# Clock_Gen.net
KiCad netlist of a schematic drawn in Altium Designer
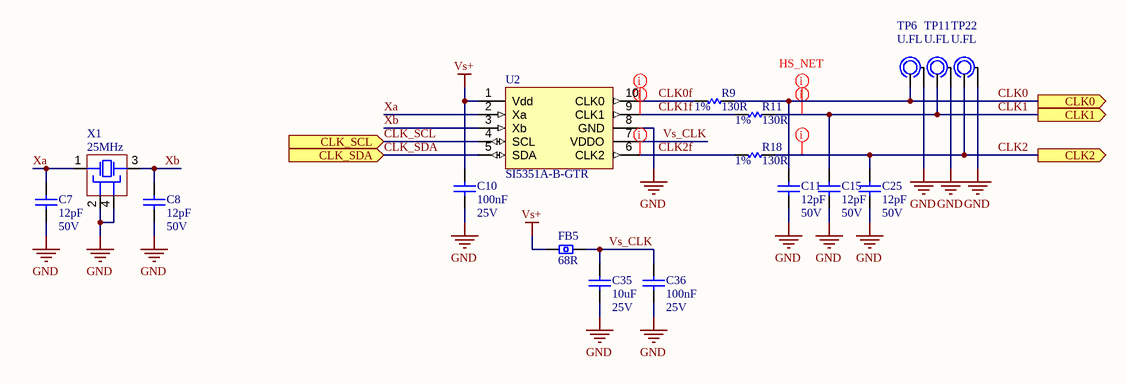
[diagram p0: Clock_Gen.SchDoc]

(export (version "E")
  (design (tool "Eeschema 10.0.6"))
  (components
    (comp (ref "C7")
      (value "12pF")
      (footprint "C0402")
      (description "Ceramic capacitor SMD-0402 12pF /50V C0G# J +-5%, Samsung, RoHS")
      (fields
        (field (name "MANUFACTURER") "Samsung")
        (field (name "MANUFACTURER PART NUMBER") "CL05C120JB5NNNC")
        (field (name "VOLTAGE") "50V")
      )
      (libsource (lib "LaserDiode_Analog") (part "CAP CER 12pF 50V C0G 0402"))
    )
    (comp (ref "C8")
      (value "12pF")
      (footprint "C0402")
      (description "Ceramic capacitor SMD-0402 12pF /50V C0G# J +-5%, Samsung, RoHS")
      (fields
        (field (name "MANUFACTURER") "Samsung")
        (field (name "MANUFACTURER PART NUMBER") "CL05C120JB5NNNC")
        (field (name "VOLTAGE") "50V")
      )
      (libsource (lib "LaserDiode_Analog") (part "CAP CER 12pF 50V C0G 0402"))
    )
    (comp (ref "C10")
      (value "100nF")
      (footprint "C0402")
      (description "Cap Ceramic 0.1uF 25V X5R 10% Pad SMD 0402 85°C T/R / Multi Layer Ceramic Capacitor (MLCC)")
      (fields
        (field (name "MANUFACTURER") "Samsung")
        (field (name "MANUFACTURER PART NUMBER") "CL05A104KA5NNNC")
        (field (name "VOLTAGE RATING") "25V")
      )
      (libsource (lib "OPAMP_DEV_SOT5_6-23") (part "CAP CER 100nF 25V X5R 0402"))
    )
    (comp (ref "C11")
      (value "12pF")
      (footprint "C0402")
      (description "Ceramic capacitor SMD-0402 12pF /50V C0G# J +-5%, Samsung, RoHS")
      (fields
        (field (name "MANUFACTURER") "Samsung")
        (field (name "MANUFACTURER PART NUMBER") "CL05C120JB5NNNC")
        (field (name "VOLTAGE") "50V")
      )
      (libsource (lib "LaserDiode_Analog") (part "CAP CER 12pF 50V C0G 0402"))
    )
    (comp (ref "C15")
      (value "12pF")
      (footprint "C0402")
      (description "Ceramic capacitor SMD-0402 12pF /50V C0G# J +-5%, Samsung, RoHS")
      (fields
        (field (name "MANUFACTURER") "Samsung")
        (field (name "MANUFACTURER PART NUMBER") "CL05C120JB5NNNC")
        (field (name "VOLTAGE") "50V")
      )
      (libsource (lib "LaserDiode_Analog") (part "CAP CER 12pF 50V C0G 0402"))
    )
    (comp (ref "C25")
      (value "12pF")
      (footprint "C0402")
      (description "Ceramic capacitor SMD-0402 12pF /50V C0G# J +-5%, Samsung, RoHS")
      (fields
        (field (name "MANUFACTURER") "Samsung")
        (field (name "MANUFACTURER PART NUMBER") "CL05C120JB5NNNC")
        (field (name "VOLTAGE") "50V")
      )
      (libsource (lib "LaserDiode_Analog") (part "CAP CER 12pF 50V C0G 0402"))
    )
    (comp (ref "C35")
      (value "10uF")
      (footprint "c0805")
      (description "Cap Ceramic 10uF 25V X5R 10% SMD 0805 85°C Embossed T/R")
      (fields
        (field (name "MANUFACTURER") "Samsung")
        (field (name "MANUFACTURER PART NUMBER") "CL21A106KAYNNNE")
        (field (name "VOLTAGE RATING") "25V")
      )
      (libsource (lib "OPAMP_DEV_SOT5_6-23") (part "CAP CER 10uF 25V X5R 0805"))
    )
    (comp (ref "C36")
      (value "100nF")
      (footprint "C0402")
      (description "Cap Ceramic 0.1uF 25V X5R 10% Pad SMD 0402 85°C T/R / Multi Layer Ceramic Capacitor (MLCC)")
      (fields
        (field (name "MANUFACTURER") "Samsung")
        (field (name "MANUFACTURER PART NUMBER") "CL05A104KA5NNNC")
        (field (name "VOLTAGE RATING") "25V")
      )
      (libsource (lib "OPAMP_DEV_SOT5_6-23") (part "CAP CER 100nF 25V X5R 0402"))
    )
    (comp (ref "FB5")
      (value "68R")
      (footprint "FB0402")
      (description "Ferrite Beads Multi-Layer 68Ohm 25% 100MHz 400mA 310mOhm DCR 0402 T/R")
      (fields
        (field (name "MANUFACTURER") "Taiyo Yuden")
        (field (name "MANUFACTURER PART NUMBER") "BK1005LL680-T")
      )
      (libsource (lib "MCU") (part "FB 68R 400mA 310mR 0402"))
    )
    (comp (ref "R9")
      (value "130R")
      (footprint "R0402")
      (description "Res General Purpose Thick Film 0402 130 Ohm 1% 1/16W ±100ppm/°C Molded SMD Paper T/R")
      (fields (field (name "TOLERANCE") "1%"))
      (libsource (lib "LaserDiode_Analog") (part "RES 130R 1% 63mW 0402"))
    )
    (comp (ref "R11")
      (value "130R")
      (footprint "R0402")
      (description "Res General Purpose Thick Film 0402 130 Ohm 1% 1/16W ±100ppm/°C Molded SMD Paper T/R")
      (fields (field (name "TOLERANCE") "1%"))
      (libsource (lib "LaserDiode_Analog") (part "RES 130R 1% 63mW 0402"))
    )
    (comp (ref "R18")
      (value "130R")
      (footprint "R0402")
      (description "Res General Purpose Thick Film 0402 130 Ohm 1% 1/16W ±100ppm/°C Molded SMD Paper T/R")
      (fields (field (name "TOLERANCE") "1%"))
      (libsource (lib "LaserDiode_Analog") (part "RES 130R 1% 63mW 0402"))
    )
    (comp (ref "TP6")
      (value "U.FL")
      (footprint "U.FL")
      (description "CONN U.FL RCPT STR 50 OHM SMD")
      (fields
        (field (name "MANUFACTURER") "Hirose")
        (field (name "MANUFACTURER PART NUMBER") "U.FL-R-SMT-1(80)")
      )
      (libsource (lib "OPAMP_DEV_SOT5_6-23") (part "TP U.FL"))
    )
    (comp (ref "TP11")
      (value "U.FL")
      (footprint "U.FL")
      (description "CONN U.FL RCPT STR 50 OHM SMD")
      (fields
        (field (name "MANUFACTURER") "Hirose")
        (field (name "MANUFACTURER PART NUMBER") "U.FL-R-SMT-1(80)")
      )
      (libsource (lib "OPAMP_DEV_SOT5_6-23") (part "TP U.FL"))
    )
    (comp (ref "TP22")
      (value "U.FL")
      (footprint "U.FL")
      (description "CONN U.FL RCPT STR 50 OHM SMD")
      (fields
        (field (name "MANUFACTURER") "Hirose")
        (field (name "MANUFACTURER PART NUMBER") "U.FL-R-SMT-1(80)")
      )
      (libsource (lib "OPAMP_DEV_SOT5_6-23") (part "TP U.FL"))
    )
    (comp (ref "U2")
      (value "SI5351A-B-GTR")
      (footprint "TSSOP50P490X110-10N")
      (libsource (lib "LaserDiode_Analog") (part "IC CLK GEN 200MHz 3 chan SI5351A-B-GTR"))
    )
    (comp (ref "X1")
      (value "25MHz")
      (footprint "XTAL FA-238V 3.2x2.5mm")
      (description "Crystal 25MHz ±50ppm (Tol) ±30ppm (Stability) 12pF FUND 50Ohm 4-Pin CSMD T/R")
      (fields
        (field (name "MANUFACTURER") "Epson")
        (field (name "MANUFACTURER PART NUMBER") "FA-23825.0000MB-W0")
      )
      (libsource (lib "LaserDiode_Analog") (part "XTAL 25MHz 50ppm 12pF 3.2x2.5mm"))
    )
  )
  (nets
    (net (code "1") (name "/CLK0") (class "Default")
      (node (ref "C11") (pin "2") (pinfunction "2_2") (pintype "passive"))
      (node (ref "R9") (pin "1") (pinfunction "1_1") (pintype "passive"))
      (node (ref "TP6") (pin "1") (pinfunction "1_1") (pintype "passive"))
    )
    (net (code "2") (name "/CLK0f") (class "Default")
      (node (ref "R9") (pin "2") (pinfunction "2_2") (pintype "passive"))
      (node (ref "U2") (pin "10") (pinfunction "CLK0_10") (pintype "output"))
    )
    (net (code "3") (name "/CLK1") (class "Default")
      (node (ref "C15") (pin "2") (pinfunction "2_2") (pintype "passive"))
      (node (ref "R11") (pin "1") (pinfunction "1_1") (pintype "passive"))
      (node (ref "TP11") (pin "1") (pinfunction "1_1") (pintype "passive"))
    )
    (net (code "4") (name "/CLK1f") (class "Default")
      (node (ref "R11") (pin "2") (pinfunction "2_2") (pintype "passive"))
      (node (ref "U2") (pin "9") (pinfunction "CLK1_9") (pintype "output"))
    )
    (net (code "5") (name "/CLK2") (class "Default")
      (node (ref "C25") (pin "2") (pinfunction "2_2") (pintype "passive"))
      (node (ref "R18") (pin "1") (pinfunction "1_1") (pintype "passive"))
      (node (ref "TP22") (pin "1") (pinfunction "1_1") (pintype "passive"))
    )
    (net (code "6") (name "/CLK2f") (class "Default")
      (node (ref "R18") (pin "2") (pinfunction "2_2") (pintype "passive"))
      (node (ref "U2") (pin "6") (pinfunction "CLK2_6") (pintype "output"))
    )
    (net (code "7") (name "/CLK_SCL") (class "Default")
      (node (ref "U2") (pin "4") (pinfunction "SCL_4") (pintype "bidirectional"))
    )
    (net (code "8") (name "/CLK_SDA") (class "Default")
      (node (ref "U2") (pin "5") (pinfunction "SDA_5") (pintype "bidirectional"))
    )
    (net (code "9") (name "/Vs_CLK") (class "Default")
      (node (ref "C35") (pin "2") (pinfunction "2_2") (pintype "passive"))
      (node (ref "C36") (pin "1") (pinfunction "1_1") (pintype "passive"))
      (node (ref "FB5") (pin "1") (pintype "passive"))
      (node (ref "U2") (pin "7") (pinfunction "VDDO_7") (pintype "power_in"))
    )
    (net (code "10") (name "/Xa") (class "Default")
      (node (ref "C7") (pin "2") (pinfunction "2_2") (pintype "passive"))
      (node (ref "U2") (pin "2") (pinfunction "Xa_2") (pintype "input"))
      (node (ref "X1") (pin "1") (pinfunction "1_1") (pintype "passive"))
    )
    (net (code "11") (name "/Xb") (class "Default")
      (node (ref "C8") (pin "2") (pinfunction "2_2") (pintype "passive"))
      (node (ref "U2") (pin "3") (pinfunction "Xb_3") (pintype "input"))
      (node (ref "X1") (pin "3") (pinfunction "3_3") (pintype "passive"))
    )
    (net (code "12") (name "GND") (class "Default")
      (node (ref "C10") (pin "2") (pinfunction "2_2") (pintype "passive"))
      (node (ref "C11") (pin "1") (pinfunction "1_1") (pintype "passive"))
      (node (ref "C15") (pin "1") (pinfunction "1_1") (pintype "passive"))
      (node (ref "C25") (pin "1") (pinfunction "1_1") (pintype "passive"))
      (node (ref "C35") (pin "1") (pinfunction "1_1") (pintype "passive"))
      (node (ref "C36") (pin "2") (pinfunction "2_2") (pintype "passive"))
      (node (ref "C7") (pin "1") (pinfunction "1_1") (pintype "passive"))
      (node (ref "C8") (pin "1") (pinfunction "1_1") (pintype "passive"))
      (node (ref "TP11") (pin "0") (pinfunction "0_0") (pintype "passive"))
      (node (ref "TP22") (pin "0") (pinfunction "0_0") (pintype "passive"))
      (node (ref "TP6") (pin "0") (pinfunction "0_0") (pintype "passive"))
      (node (ref "U2") (pin "8") (pinfunction "GND_8") (pintype "power_in"))
      (node (ref "X1") (pin "2") (pinfunction "2_2") (pintype "passive"))
      (node (ref "X1") (pin "4") (pinfunction "4_4") (pintype "passive"))
    )
    (net (code "13") (name "Vs+") (class "Default")
      (node (ref "C10") (pin "1") (pinfunction "1_1") (pintype "passive"))
      (node (ref "FB5") (pin "2") (pintype "passive"))
      (node (ref "U2") (pin "1") (pinfunction "Vdd_1") (pintype "power_in"))
    )
  )
)
